# as14120_x31_adc.net
KiCad netlist of a schematic drawn in Altium Designer
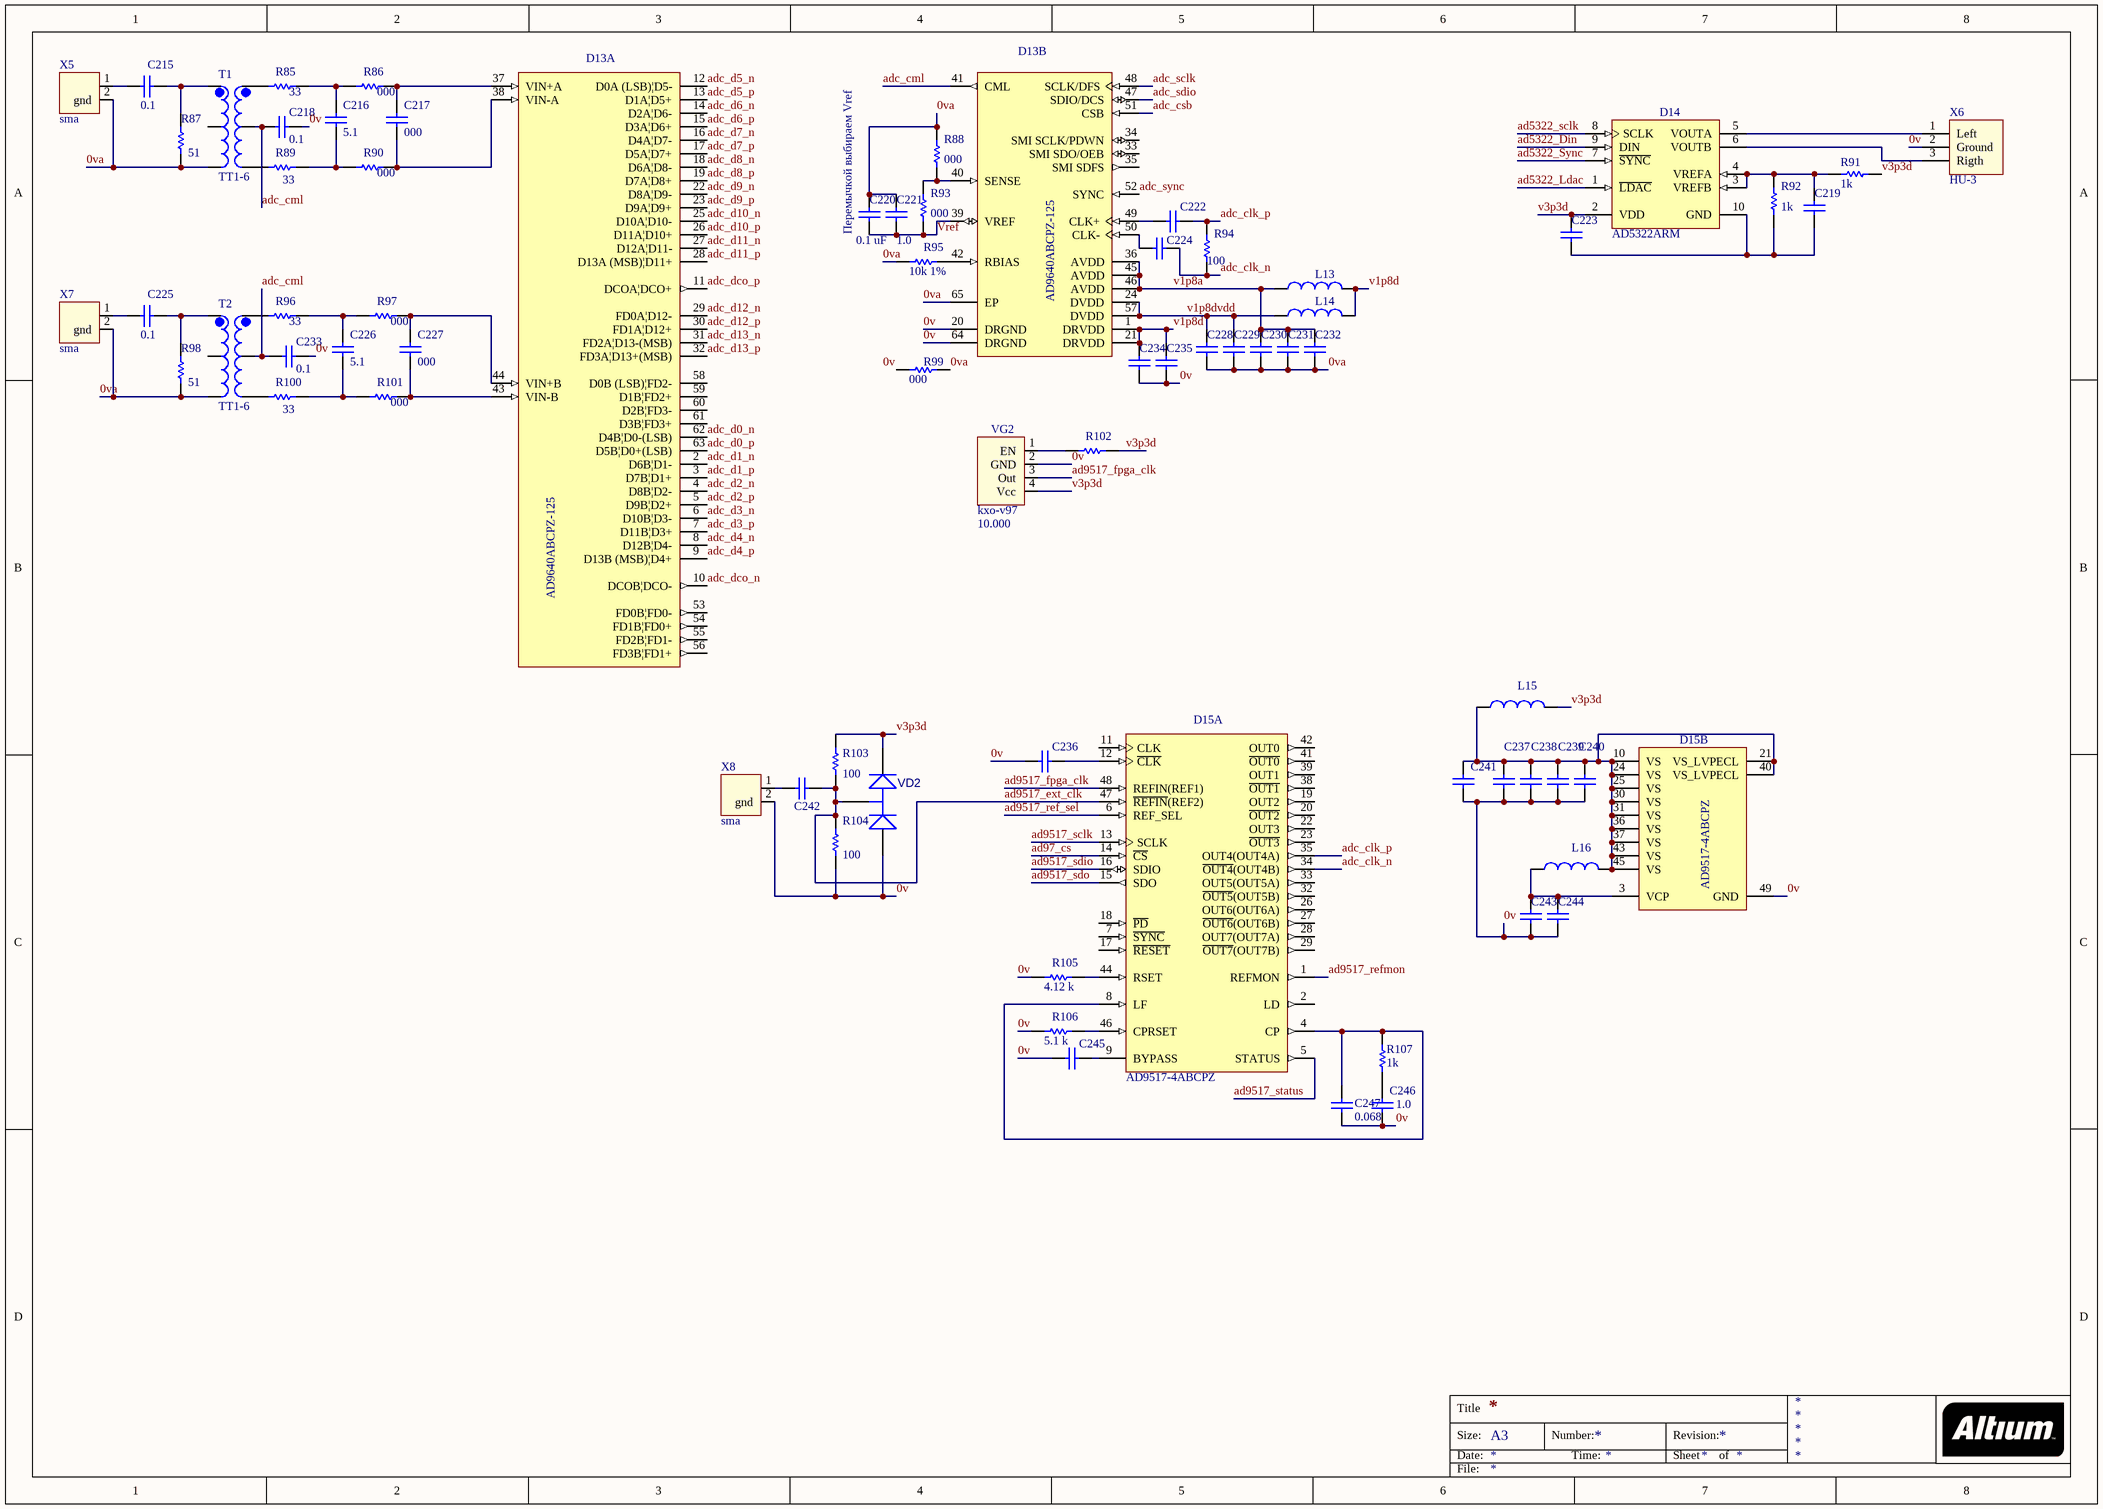
[diagram p0: as14120_x31_adc.SchDoc]

(export (version "E")
  (design (tool "Eeschema 10.0.6"))
  (components
    (comp (ref "C215")
      (value "0.1")
      (footprint "CAPC0402(1005)60_M")
      (description "CAP 1uF 10V ±20% 0402 (1005 Metric) Thickness 0.6mm SMD")
      (fields (field (name "TOLERANCE") "±20%") (field (name "Comment") "CAP 1uF 10V 0402(1005)"))
      (libsource (lib "as14120") (part "CAP_0402"))
    )
    (comp (ref "C216")
      (value "5.1")
      (footprint "CAPC0805(2012)100_N")
      (fields (field (name "Comment") "CAP_0805"))
      (libsource (lib "as14120") (part "CAP_0805"))
    )
    (comp (ref "C217")
      (value "000")
      (footprint "CAPC0805(2012)100_N")
      (fields (field (name "Comment") "CAP_0805"))
      (libsource (lib "as14120") (part "CAP_0805"))
    )
    (comp (ref "C218")
      (value "0.1")
      (footprint "CAPC0402(1005)60_M")
      (description "CAP 1uF 10V ±20% 0402 (1005 Metric) Thickness 0.6mm SMD")
      (fields (field (name "TOLERANCE") "±20%") (field (name "Comment") "CAP 1uF 10V 0402(1005)"))
      (libsource (lib "as14120") (part "CAP_0402"))
    )
    (comp (ref "C219")
      (value "CAP 1uF 10V 0402(1005)")
      (footprint "CAPC0402(1005)60_M")
      (description "CAP 1uF 10V ±20% 0402 (1005 Metric) Thickness 0.6mm SMD")
      (fields (field (name "TOLERANCE") "±20%"))
      (libsource (lib "as14120") (part "CAP_0402"))
    )
    (comp (ref "C220")
      (value "0.1 uF")
      (footprint "CAPC0402(1005)60_M")
      (description "CAP 1uF 10V ±20% 0402 (1005 Metric) Thickness 0.6mm SMD")
      (fields (field (name "TOLERANCE") "±20%") (field (name "Comment") "CAP 1uF 10V 0402(1005)"))
      (libsource (lib "as14120") (part "CAP_0402"))
    )
    (comp (ref "C221")
      (value "1.0")
      (footprint "CAPC0402(1005)60_M")
      (description "CAP 1uF 10V ±20% 0402 (1005 Metric) Thickness 0.6mm SMD")
      (fields (field (name "TOLERANCE") "±20%") (field (name "Comment") "CAP 1uF 10V 0402(1005)"))
      (libsource (lib "as14120") (part "CAP_0402"))
    )
    (comp (ref "C222")
      (value "CAP 1uF 10V 0402(1005)")
      (footprint "CAPC0402(1005)60_M")
      (description "CAP 1uF 10V ±20% 0402 (1005 Metric) Thickness 0.6mm SMD")
      (fields (field (name "TOLERANCE") "±20%"))
      (libsource (lib "as14120") (part "CAP_0402"))
    )
    (comp (ref "C223")
      (value "CAP 1uF 10V 0402(1005)")
      (footprint "CAPC0402(1005)60_M")
      (description "CAP 1uF 10V ±20% 0402 (1005 Metric) Thickness 0.6mm SMD")
      (fields (field (name "TOLERANCE") "±20%"))
      (libsource (lib "as14120") (part "CAP_0402"))
    )
    (comp (ref "C224")
      (value "CAP 1uF 10V 0402(1005)")
      (footprint "CAPC0402(1005)60_M")
      (description "CAP 1uF 10V ±20% 0402 (1005 Metric) Thickness 0.6mm SMD")
      (fields (field (name "TOLERANCE") "±20%"))
      (libsource (lib "as14120") (part "CAP_0402"))
    )
    (comp (ref "C225")
      (value "0.1")
      (footprint "CAPC0402(1005)60_M")
      (description "CAP 1uF 10V ±20% 0402 (1005 Metric) Thickness 0.6mm SMD")
      (fields (field (name "TOLERANCE") "±20%") (field (name "Comment") "CAP 1uF 10V 0402(1005)"))
      (libsource (lib "as14120") (part "CAP_0402"))
    )
    (comp (ref "C226")
      (value "5.1")
      (footprint "CAPC0805(2012)100_N")
      (fields (field (name "Comment") "CAP_0805"))
      (libsource (lib "as14120") (part "CAP_0805"))
    )
    (comp (ref "C227")
      (value "000")
      (footprint "CAPC0805(2012)100_N")
      (fields (field (name "Comment") "CAP_0805"))
      (libsource (lib "as14120") (part "CAP_0805"))
    )
    (comp (ref "C228")
      (value "CAP 1uF 10V 0402(1005)")
      (footprint "CAPC0402(1005)60_M")
      (description "CAP 1uF 10V ±20% 0402 (1005 Metric) Thickness 0.6mm SMD")
      (fields (field (name "TOLERANCE") "±20%"))
      (libsource (lib "as14120") (part "CAP_0402"))
    )
    (comp (ref "C229")
      (value "CAP 1uF 10V 0402(1005)")
      (footprint "CAPC0402(1005)60_M")
      (description "CAP 1uF 10V ±20% 0402 (1005 Metric) Thickness 0.6mm SMD")
      (fields (field (name "TOLERANCE") "±20%"))
      (libsource (lib "as14120") (part "CAP_0402"))
    )
    (comp (ref "C230")
      (value "CAP 1uF 10V 0402(1005)")
      (footprint "CAPC0402(1005)60_M")
      (description "CAP 1uF 10V ±20% 0402 (1005 Metric) Thickness 0.6mm SMD")
      (fields (field (name "TOLERANCE") "±20%"))
      (libsource (lib "as14120") (part "CAP_0402"))
    )
    (comp (ref "C231")
      (value "CAP 1uF 10V 0402(1005)")
      (footprint "CAPC0402(1005)60_M")
      (description "CAP 1uF 10V ±20% 0402 (1005 Metric) Thickness 0.6mm SMD")
      (fields (field (name "TOLERANCE") "±20%"))
      (libsource (lib "as14120") (part "CAP_0402"))
    )
    (comp (ref "C232")
      (value "CAP 1uF 10V 0402(1005)")
      (footprint "CAPC0402(1005)60_M")
      (description "CAP 1uF 10V ±20% 0402 (1005 Metric) Thickness 0.6mm SMD")
      (fields (field (name "TOLERANCE") "±20%"))
      (libsource (lib "as14120") (part "CAP_0402"))
    )
    (comp (ref "C233")
      (value "0.1")
      (footprint "CAPC0402(1005)60_M")
      (description "CAP 1uF 10V ±20% 0402 (1005 Metric) Thickness 0.6mm SMD")
      (fields (field (name "TOLERANCE") "±20%") (field (name "Comment") "CAP 1uF 10V 0402(1005)"))
      (libsource (lib "as14120") (part "CAP_0402"))
    )
    (comp (ref "C234")
      (value "CAP 1uF 10V 0402(1005)")
      (footprint "CAPC0402(1005)60_M")
      (description "CAP 1uF 10V ±20% 0402 (1005 Metric) Thickness 0.6mm SMD")
      (fields (field (name "TOLERANCE") "±20%"))
      (libsource (lib "as14120") (part "CAP_0402"))
    )
    (comp (ref "C235")
      (value "CAP 1uF 10V 0402(1005)")
      (footprint "CAPC0402(1005)60_M")
      (description "CAP 1uF 10V ±20% 0402 (1005 Metric) Thickness 0.6mm SMD")
      (fields (field (name "TOLERANCE") "±20%"))
      (libsource (lib "as14120") (part "CAP_0402"))
    )
    (comp (ref "C236")
      (value "CAP 1uF 10V 0402(1005)")
      (footprint "CAPC0402(1005)60_M")
      (description "CAP 1uF 10V ±20% 0402 (1005 Metric) Thickness 0.6mm SMD")
      (fields (field (name "TOLERANCE") "±20%"))
      (libsource (lib "as14120") (part "CAP_0402"))
    )
    (comp (ref "C237")
      (value "CAP 1uF 10V 0402(1005)")
      (footprint "CAPC0402(1005)60_M")
      (description "CAP 1uF 10V ±20% 0402 (1005 Metric) Thickness 0.6mm SMD")
      (fields (field (name "TOLERANCE") "±20%"))
      (libsource (lib "as14120") (part "CAP_0402"))
    )
    (comp (ref "C238")
      (value "CAP 1uF 10V 0402(1005)")
      (footprint "CAPC0402(1005)60_M")
      (description "CAP 1uF 10V ±20% 0402 (1005 Metric) Thickness 0.6mm SMD")
      (fields (field (name "TOLERANCE") "±20%"))
      (libsource (lib "as14120") (part "CAP_0402"))
    )
    (comp (ref "C239")
      (value "CAP 1uF 10V 0402(1005)")
      (footprint "CAPC0402(1005)60_M")
      (description "CAP 1uF 10V ±20% 0402 (1005 Metric) Thickness 0.6mm SMD")
      (fields (field (name "TOLERANCE") "±20%"))
      (libsource (lib "as14120") (part "CAP_0402"))
    )
    (comp (ref "C240")
      (value "CAP 1uF 10V 0402(1005)")
      (footprint "CAPC0402(1005)60_M")
      (description "CAP 1uF 10V ±20% 0402 (1005 Metric) Thickness 0.6mm SMD")
      (fields (field (name "TOLERANCE") "±20%"))
      (libsource (lib "as14120") (part "CAP_0402"))
    )
    (comp (ref "C241")
      (value "CAP 1uF 10V 0402(1005)")
      (footprint "CAPC0402(1005)60_M")
      (description "CAP 1uF 10V ±20% 0402 (1005 Metric) Thickness 0.6mm SMD")
      (fields (field (name "TOLERANCE") "±20%"))
      (libsource (lib "as14120") (part "CAP_0402"))
    )
    (comp (ref "C242")
      (value "CAP 1uF 10V 0402(1005)")
      (footprint "CAPC0402(1005)60_M")
      (description "CAP 1uF 10V ±20% 0402 (1005 Metric) Thickness 0.6mm SMD")
      (fields (field (name "TOLERANCE") "±20%"))
      (libsource (lib "as14120") (part "CAP_0402"))
    )
    (comp (ref "C243")
      (value "CAP 1uF 10V 0402(1005)")
      (footprint "CAPC0402(1005)60_M")
      (description "CAP 1uF 10V ±20% 0402 (1005 Metric) Thickness 0.6mm SMD")
      (fields (field (name "TOLERANCE") "±20%"))
      (libsource (lib "as14120") (part "CAP_0402"))
    )
    (comp (ref "C244")
      (value "CAP 1uF 10V 0402(1005)")
      (footprint "CAPC0402(1005)60_M")
      (description "CAP 1uF 10V ±20% 0402 (1005 Metric) Thickness 0.6mm SMD")
      (fields (field (name "TOLERANCE") "±20%"))
      (libsource (lib "as14120") (part "CAP_0402"))
    )
    (comp (ref "C245")
      (value "CAP 1uF 10V 0402(1005)")
      (footprint "CAPC0402(1005)60_M")
      (description "CAP 1uF 10V ±20% 0402 (1005 Metric) Thickness 0.6mm SMD")
      (fields (field (name "TOLERANCE") "±20%"))
      (libsource (lib "as14120") (part "CAP_0402"))
    )
    (comp (ref "C246")
      (value "1.0")
      (footprint "CAPC0805(2012)100_N")
      (fields (field (name "Comment") "CAP_0805"))
      (libsource (lib "as14120") (part "CAP_0805"))
    )
    (comp (ref "C247")
      (value "0.068")
      (footprint "CAPC0805(2012)100_N")
      (fields (field (name "Comment") "CAP_0805"))
      (libsource (lib "as14120") (part "CAP_0805"))
    )
    (comp (ref "D13")
      (value "AD9640ABCPZ-125")
      (footprint "CP-64-6_N")
      (fields (field (name "PART NUMBER") "AD9640-125") (field (name "MANUFACTURER") "Analog Devices"))
      (libsource (lib "Analog Devices Data Converters Analog-to-Digital Converters") (part "AD9640ABCPZ-125"))
    )
    (comp (ref "D14")
      (value "AD5322ARM")
      (footprint "RM-10_L")
      (fields (field (name "ADI PART NUMBER") "AD5322") (field (name "MANUFACTURER") "Analog Devices"))
      (libsource (lib "Analog Devices Data Converters Digital-to-Analog Converters") (part "AD5322ARM"))
    )
    (comp (ref "D15")
      (value "AD9517-4ABCPZ")
      (footprint "ADI-CP-48-8_L")
      (libsource (lib "Analog Devices RF IF Timing ICs and Clocks") (part "AD9517-4ABCPZ"))
    )
    (comp (ref "L13")
      (value "BLM21PG300SN1D")
      (footprint "CAPC0805(2012)100_N")
      (libsource (lib "as14120") (part "Ferrite_beat"))
    )
    (comp (ref "L14")
      (value "BLM21PG300SN1D")
      (footprint "CAPC0805(2012)100_N")
      (libsource (lib "as14120") (part "Ferrite_beat"))
    )
    (comp (ref "L15")
      (value "BLM21PG300SN1D")
      (footprint "CAPC0805(2012)100_N")
      (libsource (lib "as14120") (part "Ferrite_beat"))
    )
    (comp (ref "L16")
      (value "BLM21PG300SN1D")
      (footprint "CAPC0805(2012)100_N")
      (libsource (lib "as14120") (part "Ferrite_beat"))
    )
    (comp (ref "R85")
      (value "33")
      (footprint "RESC0805(2012)_L")
      (description "1K 0.125W 1% 0805 (2012 Metric)  SMD")
      (fields (field (name "TOLERANCE") "1 %") (field (name "POWER") "0.125 W"))
      (libsource (lib "as14120") (part "RES_0805"))
    )
    (comp (ref "R86")
      (value "000")
      (footprint "RESC0805(2012)_L")
      (description "1K 0.125W 1% 0805 (2012 Metric)  SMD")
      (fields (field (name "TOLERANCE") "1 %") (field (name "POWER") "0.125 W"))
      (libsource (lib "as14120") (part "RES_0805"))
    )
    (comp (ref "R87")
      (value "51")
      (footprint "RESC0805(2012)_L")
      (description "1K 0.125W 1% 0805 (2012 Metric)  SMD")
      (fields (field (name "TOLERANCE") "1 %") (field (name "POWER") "0.125 W"))
      (libsource (lib "as14120") (part "RES_0805"))
    )
    (comp (ref "R88")
      (value "000")
      (footprint "RESC0603(1608)_L")
      (description "1K 0.1W 5% 0603 (1608 Metric)  SMD")
      (fields (field (name "TOLERANCE") "5 %") (field (name "POWER") "0.1 W"))
      (libsource (lib "as14120") (part "RES_0603"))
    )
    (comp (ref "R89")
      (value "33")
      (footprint "RESC0805(2012)_L")
      (description "1K 0.125W 1% 0805 (2012 Metric)  SMD")
      (fields (field (name "TOLERANCE") "1 %") (field (name "POWER") "0.125 W"))
      (libsource (lib "as14120") (part "RES_0805"))
    )
    (comp (ref "R90")
      (value "000")
      (footprint "RESC0805(2012)_L")
      (description "1K 0.125W 1% 0805 (2012 Metric)  SMD")
      (fields (field (name "TOLERANCE") "1 %") (field (name "POWER") "0.125 W"))
      (libsource (lib "as14120") (part "RES_0805"))
    )
    (comp (ref "R91")
      (value "1k")
      (footprint "RESC0603(1608)_L")
      (description "1K 0.1W 5% 0603 (1608 Metric)  SMD")
      (fields (field (name "TOLERANCE") "5 %") (field (name "POWER") "0.1 W"))
      (libsource (lib "as14120") (part "RES_0603"))
    )
    (comp (ref "R92")
      (value "1k")
      (footprint "RESC0603(1608)_L")
      (description "1K 0.1W 5% 0603 (1608 Metric)  SMD")
      (fields (field (name "TOLERANCE") "5 %") (field (name "POWER") "0.1 W"))
      (libsource (lib "as14120") (part "RES_0603"))
    )
    (comp (ref "R93")
      (value "000")
      (footprint "RESC0603(1608)_L")
      (description "1K 0.1W 5% 0603 (1608 Metric)  SMD")
      (fields (field (name "TOLERANCE") "5 %") (field (name "POWER") "0.1 W"))
      (libsource (lib "as14120") (part "RES_0603"))
    )
    (comp (ref "R94")
      (value "100")
      (footprint "RESC0805(2012)_L")
      (description "1K 0.125W 1% 0805 (2012 Metric)  SMD")
      (fields (field (name "TOLERANCE") "1 %") (field (name "POWER") "0.125 W"))
      (libsource (lib "as14120") (part "RES_0805"))
    )
    (comp (ref "R95")
      (value "10k 1%")
      (footprint "RESC0805(2012)_L")
      (description "1K 0.125W 1% 0805 (2012 Metric)  SMD")
      (fields (field (name "TOLERANCE") "1 %") (field (name "POWER") "0.125 W"))
      (libsource (lib "as14120") (part "RES_0805"))
    )
    (comp (ref "R96")
      (value "33")
      (footprint "RESC0805(2012)_L")
      (description "1K 0.125W 1% 0805 (2012 Metric)  SMD")
      (fields (field (name "TOLERANCE") "1 %") (field (name "POWER") "0.125 W"))
      (libsource (lib "as14120") (part "RES_0805"))
    )
    (comp (ref "R97")
      (value "000")
      (footprint "RESC0805(2012)_L")
      (description "1K 0.125W 1% 0805 (2012 Metric)  SMD")
      (fields (field (name "TOLERANCE") "1 %") (field (name "POWER") "0.125 W"))
      (libsource (lib "as14120") (part "RES_0805"))
    )
    (comp (ref "R98")
      (value "51")
      (footprint "RESC0805(2012)_L")
      (description "1K 0.125W 1% 0805 (2012 Metric)  SMD")
      (fields (field (name "TOLERANCE") "1 %") (field (name "POWER") "0.125 W"))
      (libsource (lib "as14120") (part "RES_0805"))
    )
    (comp (ref "R99")
      (value "000")
      (footprint "RESC0603(1608)_L")
      (description "1K 0.1W 5% 0603 (1608 Metric)  SMD")
      (fields (field (name "TOLERANCE") "5 %") (field (name "POWER") "0.1 W"))
      (libsource (lib "as14120") (part "RES_0603"))
    )
    (comp (ref "R100")
      (value "33")
      (footprint "RESC0805(2012)_L")
      (description "1K 0.125W 1% 0805 (2012 Metric)  SMD")
      (fields (field (name "TOLERANCE") "1 %") (field (name "POWER") "0.125 W"))
      (libsource (lib "as14120") (part "RES_0805"))
    )
    (comp (ref "R101")
      (value "000")
      (footprint "RESC0805(2012)_L")
      (description "1K 0.125W 1% 0805 (2012 Metric)  SMD")
      (fields (field (name "TOLERANCE") "1 %") (field (name "POWER") "0.125 W"))
      (libsource (lib "as14120") (part "RES_0805"))
    )
    (comp (ref "R102")
      (value "1K 5% 0603(1608)")
      (footprint "RESC0603(1608)_L")
      (description "1K 0.1W 5% 0603 (1608 Metric)  SMD")
      (fields (field (name "TOLERANCE") "5 %") (field (name "POWER") "0.1 W"))
      (libsource (lib "as14120") (part "RES_0603"))
    )
    (comp (ref "R103")
      (value "100")
      (footprint "RESC0805(2012)_L")
      (description "1K 0.125W 1% 0805 (2012 Metric)  SMD")
      (fields (field (name "TOLERANCE") "1 %") (field (name "POWER") "0.125 W"))
      (libsource (lib "as14120") (part "RES_0805"))
    )
    (comp (ref "R104")
      (value "100")
      (footprint "RESC0805(2012)_L")
      (description "1K 0.125W 1% 0805 (2012 Metric)  SMD")
      (fields (field (name "TOLERANCE") "1 %") (field (name "POWER") "0.125 W"))
      (libsource (lib "as14120") (part "RES_0805"))
    )
    (comp (ref "R105")
      (value "4.12 k")
      (footprint "RESC0805(2012)_L")
      (description "1K 0.125W 1% 0805 (2012 Metric)  SMD")
      (fields (field (name "TOLERANCE") "1 %") (field (name "POWER") "0.125 W"))
      (libsource (lib "as14120") (part "RES_0805"))
    )
    (comp (ref "R106")
      (value "5.1 k")
      (footprint "RESC0805(2012)_L")
      (description "1K 0.125W 1% 0805 (2012 Metric)  SMD")
      (fields (field (name "TOLERANCE") "1 %") (field (name "POWER") "0.125 W"))
      (libsource (lib "as14120") (part "RES_0805"))
    )
    (comp (ref "R107")
      (value "1k")
      (footprint "RESC0805(2012)_L")
      (description "1K 0.125W 1% 0805 (2012 Metric)  SMD")
      (fields (field (name "TOLERANCE") "1 %") (field (name "POWER") "0.125 W"))
      (libsource (lib "as14120") (part "RES_0805"))
    )
    (comp (ref "T1") (value "TT1-6") (footprint "TT!-6-KK81") (libsource (lib "as14120") (part "TT1-6-KK81")))
    (comp (ref "T2") (value "TT1-6") (footprint "TT!-6-KK81") (libsource (lib "as14120") (part "TT1-6-KK81")))
    (comp (ref "VD2")
      (value "BAV99")
      (footprint "SO-G3/X.9")
      (description "SOT23 Silicon Planar High-Speed Switching Series Diode Pair")
      (libsource (lib "alexsb") (part "BAV99"))
    )
    (comp (ref "VG2")
      (value "kxo-v97")
      (footprint "kxo-v97")
      (fields (field (name "ALTIUM_VALUE") "10.000"))
      (libsource (lib "as14120") (part "kxo-v97"))
    )
    (comp (ref "X5") (value "sma") (footprint "sma") (libsource (lib "as14120") (part "sma")))
    (comp (ref "X6") (value "HU-3") (footprint "HU-3") (libsource (lib "as14120") (part "HU-3")))
    (comp (ref "X7") (value "sma") (footprint "sma") (libsource (lib "as14120") (part "sma")))
    (comp (ref "X8") (value "sma") (footprint "sma") (libsource (lib "as14120") (part "sma")))
  )
  (nets
    (net (code "1") (name "/0v") (class "Default")
      (node (ref "C218") (pin "2") (pinfunction "2_2") (pintype "passive"))
      (node (ref "C233") (pin "2") (pinfunction "2_2") (pintype "passive"))
      (node (ref "C234") (pin "1") (pinfunction "1_1") (pintype "passive"))
      (node (ref "C235") (pin "1") (pinfunction "1_1") (pintype "passive"))
      (node (ref "C236") (pin "1") (pinfunction "1_1") (pintype "passive"))
      (node (ref "C237") (pin "1") (pinfunction "1_1") (pintype "passive"))
      (node (ref "C238") (pin "1") (pinfunction "1_1") (pintype "passive"))
      (node (ref "C239") (pin "1") (pinfunction "1_1") (pintype "passive"))
      (node (ref "C240") (pin "1") (pinfunction "1_1") (pintype "passive"))
      (node (ref "C241") (pin "1") (pinfunction "1_1") (pintype "passive"))
      (node (ref "C243") (pin "1") (pinfunction "1_1") (pintype "passive"))
      (node (ref "C244") (pin "1") (pinfunction "1_1") (pintype "passive"))
      (node (ref "C245") (pin "1") (pinfunction "1_1") (pintype "passive"))
      (node (ref "C246") (pin "1") (pinfunction "1_1") (pintype "passive"))
      (node (ref "C247") (pin "1") (pinfunction "1_1") (pintype "passive"))
      (node (ref "D13") (pin "20") (pinfunction "DRGND_20") (pintype "power_in"))
      (node (ref "D13") (pin "64") (pinfunction "DRGND_64") (pintype "power_in"))
      (node (ref "D15") (pin "49") (pinfunction "GND_49") (pintype "power_in"))
      (node (ref "R104") (pin "1") (pinfunction "1_1") (pintype "passive"))
      (node (ref "R105") (pin "2") (pinfunction "2_2") (pintype "passive"))
      (node (ref "R106") (pin "2") (pinfunction "2_2") (pintype "passive"))
      (node (ref "VD2") (pin "3") (pinfunction "A_3") (pintype "passive"))
      (node (ref "VG2") (pin "2") (pinfunction "GND_2") (pintype "passive"))
      (node (ref "X6") (pin "2") (pinfunction "Ground_2") (pintype "passive"))
      (node (ref "X8") (pin "2") (pinfunction "gnd_2") (pintype "passive"))
    )
    (net (code "2") (name "/0va") (class "Default")
      (node (ref "C220") (pin "2") (pinfunction "2_2") (pintype "passive"))
      (node (ref "C221") (pin "2") (pinfunction "2_2") (pintype "passive"))
      (node (ref "C228") (pin "1") (pinfunction "1_1") (pintype "passive"))
      (node (ref "C229") (pin "1") (pinfunction "1_1") (pintype "passive"))
      (node (ref "C230") (pin "1") (pinfunction "1_1") (pintype "passive"))
      (node (ref "C231") (pin "1") (pinfunction "1_1") (pintype "passive"))
      (node (ref "C232") (pin "1") (pinfunction "1_1") (pintype "passive"))
      (node (ref "D13") (pin "65") (pinfunction "EP_65") (pintype "power_in"))
      (node (ref "R87") (pin "1") (pinfunction "1_1") (pintype "passive"))
      (node (ref "R88") (pin "1") (pinfunction "1_1") (pintype "passive"))
      (node (ref "R95") (pin "2") (pinfunction "2_2") (pintype "passive"))
      (node (ref "R98") (pin "1") (pinfunction "1_1") (pintype "passive"))
      (node (ref "R99") (pin "2") (pinfunction "2_2") (pintype "passive"))
      (node (ref "T1") (pin "6") (pinfunction "6_6") (pintype "passive"))
      (node (ref "T2") (pin "6") (pinfunction "6_6") (pintype "passive"))
      (node (ref "X5") (pin "2") (pinfunction "gnd_2") (pintype "passive"))
      (node (ref "X7") (pin "2") (pinfunction "gnd_2") (pintype "passive"))
    )
    (net (code "3") (name "/Vref") (class "Default")
      (node (ref "C220") (pin "1") (pinfunction "1_1") (pintype "passive"))
      (node (ref "C221") (pin "1") (pinfunction "1_1") (pintype "passive"))
      (node (ref "D13") (pin "39") (pinfunction "VREF_39") (pintype "bidirectional"))
      (node (ref "R93") (pin "2") (pinfunction "2_2") (pintype "passive"))
    )
    (net (code "4") (name "/ad97_cs") (class "Default")
      (node (ref "D15") (pin "14") (pinfunction "~{CS}_14") (pintype "input"))
    )
    (net (code "5") (name "/ad5322_Din") (class "Default")
      (node (ref "D14") (pin "9") (pinfunction "DIN_9") (pintype "input"))
    )
    (net (code "6") (name "/ad5322_Ldac") (class "Default")
      (node (ref "D14") (pin "1") (pinfunction "~{LDAC}_1") (pintype "input"))
    )
    (net (code "7") (name "/ad5322_Sync") (class "Default")
      (node (ref "D14") (pin "7") (pinfunction "~{SYNC}_7") (pintype "input"))
    )
    (net (code "8") (name "/ad5322_sclk") (class "Default")
      (node (ref "D14") (pin "8") (pinfunction "SCLK_8") (pintype "input"))
    )
    (net (code "9") (name "/ad9517_ext_clk") (class "Default")
      (node (ref "C242") (pin "2") (pinfunction "2_2") (pintype "passive"))
      (node (ref "D15") (pin "47") (pinfunction "~{REFIN}(REF2)_47") (pintype "input"))
      (node (ref "R103") (pin "1") (pinfunction "1_1") (pintype "passive"))
      (node (ref "R104") (pin "2") (pinfunction "2_2") (pintype "passive"))
      (node (ref "VD2") (pin "1") (pinfunction "C_1") (pintype "passive"))
    )
    (net (code "10") (name "/ad9517_fpga_clk") (class "Default")
      (node (ref "D15") (pin "48") (pinfunction "REFIN(REF1)_48") (pintype "input"))
      (node (ref "VG2") (pin "3") (pinfunction "Out_3") (pintype "passive"))
    )
    (net (code "11") (name "/ad9517_ref_sel") (class "Default")
      (node (ref "D15") (pin "6") (pinfunction "REF_SEL_6") (pintype "input"))
    )
    (net (code "12") (name "/ad9517_refmon") (class "Default")
      (node (ref "D15") (pin "1") (pinfunction "REFMON_1") (pintype "output"))
    )
    (net (code "13") (name "/ad9517_sclk") (class "Default")
      (node (ref "D15") (pin "13") (pinfunction "SCLK_13") (pintype "input"))
    )
    (net (code "14") (name "/ad9517_sdio") (class "Default")
      (node (ref "D15") (pin "16") (pinfunction "SDIO_16") (pintype "bidirectional"))
    )
    (net (code "15") (name "/ad9517_sdo") (class "Default")
      (node (ref "D15") (pin "15") (pinfunction "SDO_15") (pintype "output"))
    )
    (net (code "16") (name "/ad9517_status") (class "Default")
      (node (ref "D15") (pin "5") (pinfunction "STATUS_5") (pintype "output"))
    )
    (net (code "17") (name "/adc_clk_n") (class "Default")
      (node (ref "C224") (pin "1") (pinfunction "1_1") (pintype "passive"))
      (node (ref "D15") (pin "34") (pinfunction "~{OUT4}(OUT4B)_34") (pintype "output"))
      (node (ref "R94") (pin "1") (pinfunction "1_1") (pintype "passive"))
    )
    (net (code "18") (name "/adc_clk_p") (class "Default")
      (node (ref "C222") (pin "1") (pinfunction "1_1") (pintype "passive"))
      (node (ref "D15") (pin "35") (pinfunction "OUT4(OUT4A)_35") (pintype "output"))
      (node (ref "R94") (pin "2") (pinfunction "2_2") (pintype "passive"))
    )
    (net (code "19") (name "/adc_cml") (class "Default")
      (node (ref "C218") (pin "1") (pinfunction "1_1") (pintype "passive"))
      (node (ref "C233") (pin "1") (pinfunction "1_1") (pintype "passive"))
      (node (ref "D13") (pin "41") (pinfunction "CML_41") (pintype "output"))
      (node (ref "T1") (pin "2") (pinfunction "2_2") (pintype "passive"))
      (node (ref "T2") (pin "2") (pinfunction "2_2") (pintype "passive"))
    )
    (net (code "20") (name "/adc_csb") (class "Default")
      (node (ref "D13") (pin "51") (pinfunction "CSB_51") (pintype "input"))
    )
    (net (code "21") (name "/adc_d0_n") (class "Default")
      (node (ref "D13") (pin "62") (pinfunction "D4B¦D0-(LSB)_62") (pintype "tri_state"))
    )
    (net (code "22") (name "/adc_d0_p") (class "Default")
      (node (ref "D13") (pin "63") (pinfunction "D5B¦D0+(LSB)_63") (pintype "tri_state"))
    )
    (net (code "23") (name "/adc_d1_n") (class "Default")
      (node (ref "D13") (pin "2") (pinfunction "D6B¦D1-_2") (pintype "tri_state"))
    )
    (net (code "24") (name "/adc_d1_p") (class "Default")
      (node (ref "D13") (pin "3") (pinfunction "D7B¦D1+_3") (pintype "tri_state"))
    )
    (net (code "25") (name "/adc_d2_n") (class "Default")
      (node (ref "D13") (pin "4") (pinfunction "D8B¦D2-_4") (pintype "tri_state"))
    )
    (net (code "26") (name "/adc_d2_p") (class "Default")
      (node (ref "D13") (pin "5") (pinfunction "D9B¦D2+_5") (pintype "tri_state"))
    )
    (net (code "27") (name "/adc_d3_n") (class "Default")
      (node (ref "D13") (pin "6") (pinfunction "D10B¦D3-_6") (pintype "tri_state"))
    )
    (net (code "28") (name "/adc_d3_p") (class "Default")
      (node (ref "D13") (pin "7") (pinfunction "D11B¦D3+_7") (pintype "tri_state"))
    )
    (net (code "29") (name "/adc_d4_n") (class "Default")
      (node (ref "D13") (pin "8") (pinfunction "D12B¦D4-_8") (pintype "tri_state"))
    )
    (net (code "30") (name "/adc_d4_p") (class "Default")
      (node (ref "D13") (pin "9") (pinfunction "D13B_(MSB)¦D4+_9") (pintype "tri_state"))
    )
    (net (code "31") (name "/adc_d5_n") (class "Default")
      (node (ref "D13") (pin "12") (pinfunction "D0A_(LSB)¦D5-_12") (pintype "tri_state"))
    )
    (net (code "32") (name "/adc_d5_p") (class "Default")
      (node (ref "D13") (pin "13") (pinfunction "D1A¦D5+_13") (pintype "tri_state"))
    )
    (net (code "33") (name "/adc_d6_n") (class "Default")
      (node (ref "D13") (pin "14") (pinfunction "D2A¦D6-_14") (pintype "tri_state"))
    )
    (net (code "34") (name "/adc_d6_p") (class "Default")
      (node (ref "D13") (pin "15") (pinfunction "D3A¦D6+_15") (pintype "tri_state"))
    )
    (net (code "35") (name "/adc_d7_n") (class "Default")
      (node (ref "D13") (pin "16") (pinfunction "D4A¦D7-_16") (pintype "tri_state"))
    )
    (net (code "36") (name "/adc_d7_p") (class "Default")
      (node (ref "D13") (pin "17") (pinfunction "D5A¦D7+_17") (pintype "tri_state"))
    )
    (net (code "37") (name "/adc_d8_n") (class "Default")
      (node (ref "D13") (pin "18") (pinfunction "D6A¦D8-_18") (pintype "tri_state"))
    )
    (net (code "38") (name "/adc_d8_p") (class "Default")
      (node (ref "D13") (pin "19") (pinfunction "D7A¦D8+_19") (pintype "tri_state"))
    )
    (net (code "39") (name "/adc_d9_n") (class "Default")
      (node (ref "D13") (pin "22") (pinfunction "D8A¦D9-_22") (pintype "tri_state"))
    )
    (net (code "40") (name "/adc_d9_p") (class "Default")
      (node (ref "D13") (pin "23") (pinfunction "D9A¦D9+_23") (pintype "tri_state"))
    )
    (net (code "41") (name "/adc_d10_n") (class "Default")
      (node (ref "D13") (pin "25") (pinfunction "D10A¦D10-_25") (pintype "tri_state"))
    )
    (net (code "42") (name "/adc_d10_p") (class "Default")
      (node (ref "D13") (pin "26") (pinfunction "D11A¦D10+_26") (pintype "tri_state"))
    )
    (net (code "43") (name "/adc_d11_n") (class "Default")
      (node (ref "D13") (pin "27") (pinfunction "D12A¦D11-_27") (pintype "tri_state"))
    )
    (net (code "44") (name "/adc_d11_p") (class "Default")
      (node (ref "D13") (pin "28") (pinfunction "D13A_(MSB)¦D11+_28") (pintype "tri_state"))
    )
    (net (code "45") (name "/adc_d12_n") (class "Default")
      (node (ref "D13") (pin "29") (pinfunction "FD0A¦D12-_29") (pintype "tri_state"))
    )
    (net (code "46") (name "/adc_d12_p") (class "Default")
      (node (ref "D13") (pin "30") (pinfunction "FD1A¦D12+_30") (pintype "tri_state"))
    )
    (net (code "47") (name "/adc_d13_n") (class "Default")
      (node (ref "D13") (pin "31") (pinfunction "FD2A¦D13-(MSB)_31") (pintype "tri_state"))
    )
    (net (code "48") (name "/adc_d13_p") (class "Default")
      (node (ref "D13") (pin "32") (pinfunction "FD3A¦D13+(MSB)_32") (pintype "tri_state"))
    )
    (net (code "49") (name "/adc_dco_n") (class "Default")
      (node (ref "D13") (pin "10") (pinfunction "DCOB¦DCO-_10") (pintype "output"))
    )
    (net (code "50") (name "/adc_dco_p") (class "Default")
      (node (ref "D13") (pin "11") (pinfunction "DCOA¦DCO+_11") (pintype "output"))
    )
    (net (code "51") (name "/adc_sclk") (class "Default")
      (node (ref "D13") (pin "48") (pinfunction "SCLK/DFS_48") (pintype "input"))
    )
    (net (code "52") (name "/adc_sdio") (class "Default")
      (node (ref "D13") (pin "47") (pinfunction "SDIO/DCS_47") (pintype "bidirectional"))
    )
    (net (code "53") (name "/adc_sync") (class "Default")
      (node (ref "D13") (pin "52") (pinfunction "SYNC_52") (pintype "input"))
    )
    (net (code "54") (name "/v1p8a") (class "Default")
      (node (ref "C230") (pin "2") (pinfunction "2_2") (pintype "passive"))
      (node (ref "C231") (pin "2") (pinfunction "2_2") (pintype "passive"))
      (node (ref "C232") (pin "2") (pinfunction "2_2") (pintype "passive"))
      (node (ref "D13") (pin "36") (pinfunction "AVDD_36") (pintype "power_in"))
      (node (ref "D13") (pin "45") (pinfunction "AVDD_45") (pintype "power_in"))
      (node (ref "D13") (pin "46") (pinfunction "AVDD_46") (pintype "power_in"))
      (node (ref "L13") (pin "1") (pinfunction "1_1") (pintype "passive"))
    )
    (net (code "55") (name "/v1p8d") (class "Default")
      (node (ref "C234") (pin "2") (pinfunction "2_2") (pintype "passive"))
      (node (ref "C235") (pin "2") (pinfunction "2_2") (pintype "passive"))
      (node (ref "D13") (pin "1") (pinfunction "DRVDD_1") (pintype "power_in"))
      (node (ref "D13") (pin "21") (pinfunction "DRVDD_21") (pintype "power_in"))
      (node (ref "L13") (pin "2") (pinfunction "2_2") (pintype "passive"))
      (node (ref "L14") (pin "2") (pinfunction "2_2") (pintype "passive"))
    )
    (net (code "56") (name "/v1p8dvdd") (class "Default")
      (node (ref "C228") (pin "2") (pinfunction "2_2") (pintype "passive"))
      (node (ref "C229") (pin "2") (pinfunction "2_2") (pintype "passive"))
      (node (ref "D13") (pin "24") (pinfunction "DVDD_24") (pintype "power_in"))
      (node (ref "D13") (pin "57") (pinfunction "DVDD_57") (pintype "power_in"))
      (node (ref "L14") (pin "1") (pinfunction "1_1") (pintype "passive"))
    )
    (net (code "57") (name "/v3p3d") (class "Default")
      (node (ref "C223") (pin "2") (pinfunction "2_2") (pintype "passive"))
      (node (ref "D14") (pin "2") (pinfunction "VDD_2") (pintype "power_in"))
      (node (ref "L15") (pin "2") (pinfunction "2_2") (pintype "passive"))
      (node (ref "R102") (pin "1") (pinfunction "1_1") (pintype "passive"))
      (node (ref "R103") (pin "2") (pinfunction "2_2") (pintype "passive"))
      (node (ref "R91") (pin "2") (pinfunction "2_2") (pintype "passive"))
      (node (ref "VD2") (pin "2") (pinfunction "K_2") (pintype "passive"))
      (node (ref "VG2") (pin "4") (pinfunction "Vcc_4") (pintype "passive"))
    )
    (net (code "58") (name "Net-(C215-Pad1)") (class "Default")
      (node (ref "C215") (pin "1") (pinfunction "1_1") (pintype "passive"))
      (node (ref "X5") (pin "1") (pintype "passive"))
    )
    (net (code "59") (name "Net-(C215-Pad2)") (class "Default")
      (node (ref "C215") (pin "2") (pinfunction "2_2") (pintype "passive"))
      (node (ref "R87") (pin "2") (pinfunction "2_2") (pintype "passive"))
      (node (ref "T1") (pin "4") (pinfunction "4_4") (pintype "passive"))
    )
    (net (code "60") (name "Net-(C216-Pad1)") (class "Default")
      (node (ref "C216") (pin "1") (pinfunction "1_1") (pintype "passive"))
      (node (ref "R89") (pin "1") (pinfunction "1_1") (pintype "passive"))
      (node (ref "R90") (pin "2") (pinfunction "2_2") (pintype "passive"))
    )
    (net (code "61") (name "Net-(C216-Pad2)") (class "Default")
      (node (ref "C216") (pin "2") (pinfunction "2_2") (pintype "passive"))
      (node (ref "R85") (pin "1") (pinfunction "1_1") (pintype "passive"))
      (node (ref "R86") (pin "2") (pinfunction "2_2") (pintype "passive"))
    )
    (net (code "62") (name "Net-(C225-Pad1)") (class "Default")
      (node (ref "C225") (pin "1") (pinfunction "1_1") (pintype "passive"))
      (node (ref "X7") (pin "1") (pintype "passive"))
    )
    (net (code "63") (name "Net-(C225-Pad2)") (class "Default")
      (node (ref "C225") (pin "2") (pinfunction "2_2") (pintype "passive"))
      (node (ref "R98") (pin "2") (pinfunction "2_2") (pintype "passive"))
      (node (ref "T2") (pin "4") (pinfunction "4_4") (pintype "passive"))
    )
    (net (code "64") (name "Net-(C226-Pad1)") (class "Default")
      (node (ref "C226") (pin "1") (pinfunction "1_1") (pintype "passive"))
      (node (ref "R100") (pin "1") (pinfunction "1_1") (pintype "passive"))
      (node (ref "R101") (pin "2") (pinfunction "2_2") (pintype "passive"))
    )
    (net (code "65") (name "Net-(C226-Pad2)") (class "Default")
      (node (ref "C226") (pin "2") (pinfunction "2_2") (pintype "passive"))
      (node (ref "R96") (pin "1") (pinfunction "1_1") (pintype "passive"))
      (node (ref "R97") (pin "2") (pinfunction "2_2") (pintype "passive"))
    )
    (net (code "66") (name "Net-(C237-Pad2)") (class "Default")
      (node (ref "C237") (pin "2") (pinfunction "2_2") (pintype "passive"))
      (node (ref "C238") (pin "2") (pinfunction "2_2") (pintype "passive"))
      (node (ref "C239") (pin "2") (pinfunction "2_2") (pintype "passive"))
      (node (ref "C240") (pin "2") (pinfunction "2_2") (pintype "passive"))
      (node (ref "C241") (pin "2") (pinfunction "2_2") (pintype "passive"))
      (node (ref "D15") (pin "10") (pinfunction "VS_10") (pintype "power_in"))
      (node (ref "D15") (pin "21") (pinfunction "VS_LVPECL_21") (pintype "power_in"))
      (node (ref "D15") (pin "24") (pinfunction "VS_24") (pintype "power_in"))
      (node (ref "D15") (pin "25") (pinfunction "VS_25") (pintype "power_in"))
      (node (ref "D15") (pin "30") (pinfunction "VS_30") (pintype "power_in"))
      (node (ref "D15") (pin "31") (pinfunction "VS_31") (pintype "power_in"))
      (node (ref "D15") (pin "36") (pinfunction "VS_36") (pintype "power_in"))
      (node (ref "D15") (pin "37") (pinfunction "VS_37") (pintype "power_in"))
      (node (ref "D15") (pin "40") (pinfunction "VS_LVPECL_40") (pintype "power_in"))
      (node (ref "D15") (pin "43") (pinfunction "VS_43") (pintype "power_in"))
      (node (ref "D15") (pin "45") (pinfunction "VS_45") (pintype "power_in"))
      (node (ref "L15") (pin "1") (pinfunction "1_1") (pintype "passive"))
      (node (ref "L16") (pin "2") (pinfunction "2_2") (pintype "passive"))
    )
    (net (code "67") (name "Net-(C242-Pad1)") (class "Default")
      (node (ref "C242") (pin "1") (pinfunction "1_1") (pintype "passive"))
      (node (ref "X8") (pin "1") (pintype "passive"))
    )
    (net (code "68") (name "Net-(C246-Pad2)") (class "Default")
      (node (ref "C246") (pin "2") (pinfunction "2_2") (pintype "passive"))
      (node (ref "R107") (pin "2") (pinfunction "2_2") (pintype "passive"))
    )
    (net (code "69") (name "Net-(D13A-VIN+A)") (class "Default")
      (node (ref "C217") (pin "2") (pinfunction "2_2") (pintype "passive"))
      (node (ref "D13") (pin "37") (pinfunction "VIN+A_37") (pintype "input"))
      (node (ref "R86") (pin "1") (pinfunction "1_1") (pintype "passive"))
    )
    (net (code "70") (name "Net-(D13A-VIN+B)") (class "Default")
      (node (ref "C227") (pin "2") (pinfunction "2_2") (pintype "passive"))
      (node (ref "D13") (pin "44") (pinfunction "VIN+B_44") (pintype "input"))
      (node (ref "R97") (pin "1") (pinfunction "1_1") (pintype "passive"))
    )
    (net (code "71") (name "Net-(D13A-VIN-A)") (class "Default")
      (node (ref "C217") (pin "1") (pinfunction "1_1") (pintype "passive"))
      (node (ref "D13") (pin "38") (pinfunction "VIN-A_38") (pintype "input"))
      (node (ref "R90") (pin "1") (pinfunction "1_1") (pintype "passive"))
    )
    (net (code "72") (name "Net-(D13A-VIN-B)") (class "Default")
      (node (ref "C227") (pin "1") (pinfunction "1_1") (pintype "passive"))
      (node (ref "D13") (pin "43") (pinfunction "VIN-B_43") (pintype "input"))
      (node (ref "R101") (pin "1") (pinfunction "1_1") (pintype "passive"))
    )
    (net (code "73") (name "Net-(D13B-CLK+)") (class "Default")
      (node (ref "C222") (pin "2") (pinfunction "2_2") (pintype "passive"))
      (node (ref "D13") (pin "49") (pinfunction "CLK+_49") (pintype "input"))
    )
    (net (code "74") (name "Net-(D13B-CLK-)") (class "Default")
      (node (ref "C224") (pin "2") (pinfunction "2_2") (pintype "passive"))
      (node (ref "D13") (pin "50") (pinfunction "CLK-_50") (pintype "input"))
    )
    (net (code "75") (name "Net-(D13B-RBIAS)") (class "Default")
      (node (ref "D13") (pin "42") (pinfunction "RBIAS_42") (pintype "input"))
      (node (ref "R95") (pin "1") (pinfunction "1_1") (pintype "passive"))
    )
    (net (code "76") (name "Net-(D13B-SENSE)") (class "Default")
      (node (ref "D13") (pin "40") (pinfunction "SENSE_40") (pintype "input"))
      (node (ref "R88") (pin "2") (pinfunction "2_2") (pintype "passive"))
      (node (ref "R93") (pin "1") (pinfunction "1_1") (pintype "passive"))
    )
    (net (code "77") (name "Net-(D14-GND)") (class "Default")
      (node (ref "C219") (pin "1") (pinfunction "1_1") (pintype "passive"))
      (node (ref "C223") (pin "1") (pinfunction "1_1") (pintype "passive"))
      (node (ref "D14") (pin "10") (pinfunction "GND_10") (pintype "power_in"))
      (node (ref "R92") (pin "2") (pinfunction "2_2") (pintype "passive"))
    )
    (net (code "78") (name "Net-(D14-VOUTA)") (class "Default")
      (node (ref "D14") (pin "5") (pinfunction "VOUTA_5") (pintype "tri_state"))
      (node (ref "X6") (pin "1") (pinfunction "Left_1") (pintype "passive"))
    )
    (net (code "79") (name "Net-(D14-VOUTB)") (class "Default")
      (node (ref "D14") (pin "6") (pinfunction "VOUTB_6") (pintype "tri_state"))
      (node (ref "X6") (pin "3") (pinfunction "Rigth_3") (pintype "passive"))
    )
    (net (code "80") (name "Net-(D14-VREFA)") (class "Default")
      (node (ref "C219") (pin "2") (pinfunction "2_2") (pintype "passive"))
      (node (ref "D14") (pin "3") (pinfunction "VREFB_3") (pintype "input"))
      (node (ref "D14") (pin "4") (pinfunction "VREFA_4") (pintype "input"))
      (node (ref "R91") (pin "1") (pinfunction "1_1") (pintype "passive"))
      (node (ref "R92") (pin "1") (pinfunction "1_1") (pintype "passive"))
    )
    (net (code "81") (name "Net-(D15A-BYPASS)") (class "Default")
      (node (ref "C245") (pin "2") (pinfunction "2_2") (pintype "passive"))
      (node (ref "D15") (pin "9") (pinfunction "BYPASS_9") (pintype "passive"))
    )
    (net (code "82") (name "Net-(D15A-CP)") (class "Default")
      (node (ref "C247") (pin "2") (pinfunction "2_2") (pintype "passive"))
      (node (ref "D15") (pin "4") (pinfunction "CP_4") (pintype "output"))
      (node (ref "D15") (pin "8") (pinfunction "LF_8") (pintype "input"))
      (node (ref "R107") (pin "1") (pinfunction "1_1") (pintype "passive"))
    )
    (net (code "83") (name "Net-(D15A-CPRSET)") (class "Default")
      (node (ref "D15") (pin "46") (pinfunction "CPRSET_46") (pintype "input"))
      (node (ref "R106") (pin "1") (pinfunction "1_1") (pintype "passive"))
    )
    (net (code "84") (name "Net-(D15A-RSET)") (class "Default")
      (node (ref "D15") (pin "44") (pinfunction "RSET_44") (pintype "input"))
      (node (ref "R105") (pin "1") (pinfunction "1_1") (pintype "passive"))
    )
    (net (code "85") (name "Net-(D15A-~{CLK})") (class "Default")
      (node (ref "C236") (pin "2") (pinfunction "2_2") (pintype "passive"))
      (node (ref "D15") (pin "12") (pinfunction "~{CLK}_12") (pintype "input"))
    )
    (net (code "86") (name "Net-(D15B-VCP)") (class "Default")
      (node (ref "C243") (pin "2") (pinfunction "2_2") (pintype "passive"))
      (node (ref "C244") (pin "2") (pinfunction "2_2") (pintype "passive"))
      (node (ref "D15") (pin "3") (pinfunction "VCP_3") (pintype "power_in"))
      (node (ref "L16") (pin "1") (pinfunction "1_1") (pintype "passive"))
    )
    (net (code "87") (name "Net-(R85-Pad2)") (class "Default")
      (node (ref "R85") (pin "2") (pinfunction "2_2") (pintype "passive"))
      (node (ref "T1") (pin "3") (pinfunction "3_3") (pintype "passive"))
    )
    (net (code "88") (name "Net-(R89-Pad2)") (class "Default")
      (node (ref "R89") (pin "2") (pinfunction "2_2") (pintype "passive"))
      (node (ref "T1") (pin "1") (pinfunction "1_1") (pintype "passive"))
    )
    (net (code "89") (name "Net-(R96-Pad2)") (class "Default")
      (node (ref "R96") (pin "2") (pinfunction "2_2") (pintype "passive"))
      (node (ref "T2") (pin "3") (pinfunction "3_3") (pintype "passive"))
    )
    (net (code "90") (name "Net-(R100-Pad2)") (class "Default")
      (node (ref "R100") (pin "2") (pinfunction "2_2") (pintype "passive"))
      (node (ref "T2") (pin "1") (pinfunction "1_1") (pintype "passive"))
    )
    (net (code "91") (name "Net-(VG2-EN)") (class "Default")
      (node (ref "R102") (pin "2") (pinfunction "2_2") (pintype "passive"))
      (node (ref "VG2") (pin "1") (pinfunction "EN_1") (pintype "passive"))
    )
    (net (code "92") (name "unconnected-(D13A-D0B_(LSB)¦FD2--Pad58)") (class "Default")
      (node (ref "D13") (pin "58") (pinfunction "D0B_(LSB)¦FD2-_58") (pintype "tri_state"))
    )
    (net (code "93") (name "unconnected-(D13A-D1B¦FD2+-Pad59)") (class "Default")
      (node (ref "D13") (pin "59") (pinfunction "D1B¦FD2+_59") (pintype "tri_state"))
    )
    (net (code "94") (name "unconnected-(D13A-D2B¦FD3--Pad60)") (class "Default")
      (node (ref "D13") (pin "60") (pinfunction "D2B¦FD3-_60") (pintype "tri_state"))
    )
    (net (code "95") (name "unconnected-(D13A-D3B¦FD3+-Pad61)") (class "Default")
      (node (ref "D13") (pin "61") (pinfunction "D3B¦FD3+_61") (pintype "tri_state"))
    )
    (net (code "96") (name "unconnected-(D13A-FD0B¦FD0--Pad53)") (class "Default")
      (node (ref "D13") (pin "53") (pinfunction "FD0B¦FD0-_53") (pintype "output"))
    )
    (net (code "97") (name "unconnected-(D13A-FD1B¦FD0+-Pad54)") (class "Default")
      (node (ref "D13") (pin "54") (pinfunction "FD1B¦FD0+_54") (pintype "output"))
    )
    (net (code "98") (name "unconnected-(D13A-FD2B¦FD1--Pad55)") (class "Default")
      (node (ref "D13") (pin "55") (pinfunction "FD2B¦FD1-_55") (pintype "output"))
    )
    (net (code "99") (name "unconnected-(D13A-FD3B¦FD1+-Pad56)") (class "Default")
      (node (ref "D13") (pin "56") (pinfunction "FD3B¦FD1+_56") (pintype "output"))
    )
    (net (code "100") (name "unconnected-(D13B-SMI_SCLK{slash}PDWN-Pad34)") (class "Default")
      (node (ref "D13") (pin "34") (pinfunction "SMI_SCLK/PDWN_34") (pintype "bidirectional"))
    )
    (net (code "101") (name "unconnected-(D13B-SMI_SDFS-Pad35)") (class "Default")
      (node (ref "D13") (pin "35") (pinfunction "SMI_SDFS_35") (pintype "output"))
    )
    (net (code "102") (name "unconnected-(D13B-SMI_SDO{slash}OEB-Pad33)") (class "Default")
      (node (ref "D13") (pin "33") (pinfunction "SMI_SDO/OEB_33") (pintype "bidirectional"))
    )
    (net (code "103") (name "unconnected-(D15A-CLK-Pad11)") (class "Default")
      (node (ref "D15") (pin "11") (pinfunction "CLK_11") (pintype "input"))
    )
    (net (code "104") (name "unconnected-(D15A-LD-Pad2)") (class "Default")
      (node (ref "D15") (pin "2") (pinfunction "LD_2") (pintype "output"))
    )
    (net (code "105") (name "unconnected-(D15A-OUT0-Pad42)") (class "Default")
      (node (ref "D15") (pin "42") (pinfunction "OUT0_42") (pintype "output"))
    )
    (net (code "106") (name "unconnected-(D15A-OUT1-Pad39)") (class "Default")
      (node (ref "D15") (pin "39") (pinfunction "OUT1_39") (pintype "output"))
    )
    (net (code "107") (name "unconnected-(D15A-OUT2-Pad19)") (class "Default")
      (node (ref "D15") (pin "19") (pinfunction "OUT2_19") (pintype "output"))
    )
    (net (code "108") (name "unconnected-(D15A-OUT3-Pad22)") (class "Default")
      (node (ref "D15") (pin "22") (pinfunction "OUT3_22") (pintype "output"))
    )
    (net (code "109") (name "unconnected-(D15A-OUT5(OUT5A)-Pad33)") (class "Default")
      (node (ref "D15") (pin "33") (pinfunction "OUT5(OUT5A)_33") (pintype "output"))
    )
    (net (code "110") (name "unconnected-(D15A-OUT6(OUT6A)-Pad26)") (class "Default")
      (node (ref "D15") (pin "26") (pinfunction "OUT6(OUT6A)_26") (pintype "output"))
    )
    (net (code "111") (name "unconnected-(D15A-OUT7(OUT7A)-Pad28)") (class "Default")
      (node (ref "D15") (pin "28") (pinfunction "OUT7(OUT7A)_28") (pintype "output"))
    )
    (net (code "112") (name "unconnected-(D15A-~{OUT0}-Pad41)") (class "Default")
      (node (ref "D15") (pin "41") (pinfunction "~{OUT0}_41") (pintype "output"))
    )
    (net (code "113") (name "unconnected-(D15A-~{OUT1}-Pad38)") (class "Default")
      (node (ref "D15") (pin "38") (pinfunction "~{OUT1}_38") (pintype "output"))
    )
    (net (code "114") (name "unconnected-(D15A-~{OUT2}-Pad20)") (class "Default")
      (node (ref "D15") (pin "20") (pinfunction "~{OUT2}_20") (pintype "output"))
    )
    (net (code "115") (name "unconnected-(D15A-~{OUT3}-Pad23)") (class "Default")
      (node (ref "D15") (pin "23") (pinfunction "~{OUT3}_23") (pintype "output"))
    )
    (net (code "116") (name "unconnected-(D15A-~{OUT5}(OUT5B)-Pad32)") (class "Default")
      (node (ref "D15") (pin "32") (pinfunction "~{OUT5}(OUT5B)_32") (pintype "output"))
    )
    (net (code "117") (name "unconnected-(D15A-~{OUT6}(OUT6B)-Pad27)") (class "Default")
      (node (ref "D15") (pin "27") (pinfunction "~{OUT6}(OUT6B)_27") (pintype "output"))
    )
    (net (code "118") (name "unconnected-(D15A-~{OUT7}(OUT7B)-Pad29)") (class "Default")
      (node (ref "D15") (pin "29") (pinfunction "~{OUT7}(OUT7B)_29") (pintype "output"))
    )
    (net (code "119") (name "unconnected-(D15A-~{PD}-Pad18)") (class "Default")
      (node (ref "D15") (pin "18") (pinfunction "~{PD}_18") (pintype "input"))
    )
    (net (code "120") (name "unconnected-(D15A-~{RESET}-Pad17)") (class "Default")
      (node (ref "D15") (pin "17") (pinfunction "~{RESET}_17") (pintype "input"))
    )
    (net (code "121") (name "unconnected-(D15A-~{SYNC}-Pad7)") (class "Default")
      (node (ref "D15") (pin "7") (pinfunction "~{SYNC}_7") (pintype "input"))
    )
    (net (code "122") (name "unconnected-(R99-Pad1)") (class "Default")
      (node (ref "R99") (pin "1") (pinfunction "1_1") (pintype "passive"))
    )
    (net (code "123") (name "unconnected-(T1-Pad5)") (class "Default")
      (node (ref "T1") (pin "5") (pinfunction "5_5") (pintype "passive"))
    )
    (net (code "124") (name "unconnected-(T2-Pad5)") (class "Default")
      (node (ref "T2") (pin "5") (pinfunction "5_5") (pintype "passive"))
    )
  )
)
